# VC_Panning_Mixer_CTRL.net
KiCad netlist of a schematic drawn in EAGLE
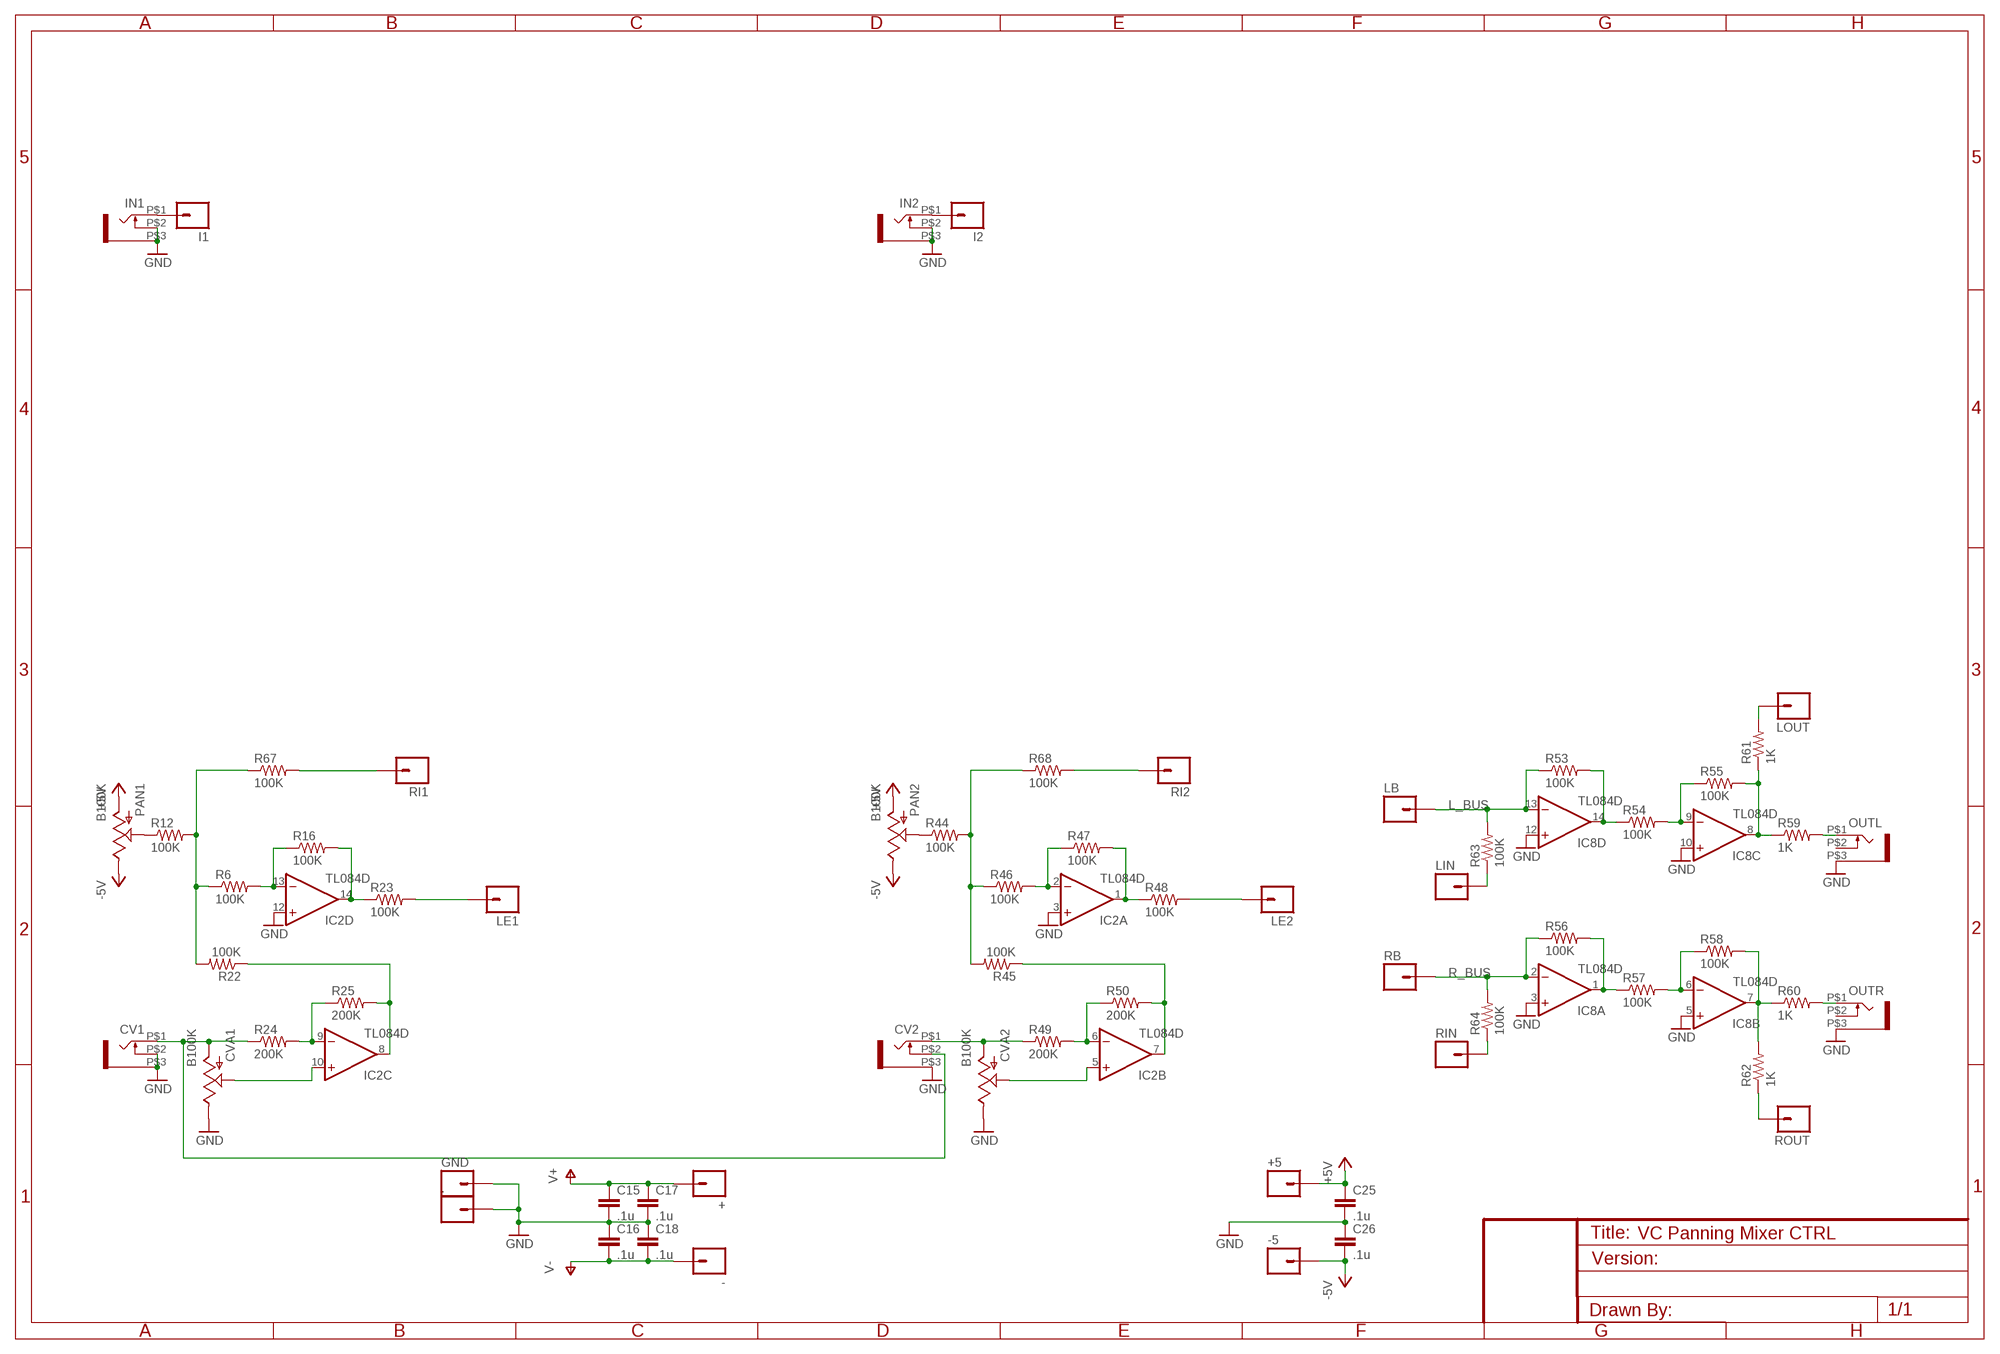
[diagram p0: schematic, sheet 1]

(export (version "E")
  (design (tool "Eeschema 10.0.6"))
  (components
    (comp (ref "+")
      (value "M01PTH")
      (footprint "eagle-import:1X01")
      (libsource (lib "eagle-import") (part "M01PTH"))
    )
    (comp (ref "+5")
      (value "M01PTH")
      (footprint "eagle-import:1X01")
      (libsource (lib "eagle-import") (part "M01PTH"))
    )
    (comp (ref "-")
      (value "M01PTH")
      (footprint "eagle-import:1X01")
      (libsource (lib "eagle-import") (part "M01PTH"))
    )
    (comp (ref "-5")
      (value "M01PTH")
      (footprint "eagle-import:1X01")
      (libsource (lib "eagle-import") (part "M01PTH"))
    )
    (comp (ref ".")
      (value "M01PTH")
      (footprint "eagle-import:1X01")
      (libsource (lib "eagle-import") (part "M01PTH"))
    )
    (comp (ref "C15")
      (value ".1u")
      (footprint "eagle-import:0805")
      (libsource (lib "eagle-import") (part "CAP0805"))
    )
    (comp (ref "C16")
      (value ".1u")
      (footprint "eagle-import:0805")
      (libsource (lib "eagle-import") (part "CAP0805"))
    )
    (comp (ref "C17")
      (value ".1u")
      (footprint "eagle-import:0805")
      (libsource (lib "eagle-import") (part "CAP0805"))
    )
    (comp (ref "C18")
      (value ".1u")
      (footprint "eagle-import:0805")
      (libsource (lib "eagle-import") (part "CAP0805"))
    )
    (comp (ref "C25")
      (value ".1u")
      (footprint "eagle-import:0805")
      (libsource (lib "eagle-import") (part "CAP0805"))
    )
    (comp (ref "C26")
      (value ".1u")
      (footprint "eagle-import:0805")
      (libsource (lib "eagle-import") (part "CAP0805"))
    )
    (comp (ref "CV1")
      (value "WQP-PJ301M-12_JACK")
      (footprint "eagle-import:WQP-PJ301M-12_JACK")
      (libsource (lib "eagle-import") (part "WQP-PJ301M-12_JACK"))
    )
    (comp (ref "CV2")
      (value "WQP-PJ301M-12_JACK")
      (footprint "eagle-import:WQP-PJ301M-12_JACK")
      (libsource (lib "eagle-import") (part "WQP-PJ301M-12_JACK"))
    )
    (comp (ref "CVA1")
      (value "B100K")
      (footprint "eagle-import:ALPS_POT")
      (libsource (lib "eagle-import") (part "POT"))
    )
    (comp (ref "CVA2")
      (value "B100K")
      (footprint "eagle-import:ALPS_POT")
      (libsource (lib "eagle-import") (part "POT"))
    )
    (comp (ref "GND")
      (value "M01PTH")
      (footprint "eagle-import:1X01")
      (libsource (lib "eagle-import") (part "M01PTH"))
    )
    (comp (ref "I1")
      (value "M01PTH")
      (footprint "eagle-import:1X01")
      (libsource (lib "eagle-import") (part "M01PTH"))
    )
    (comp (ref "I2")
      (value "M01PTH")
      (footprint "eagle-import:1X01")
      (libsource (lib "eagle-import") (part "M01PTH"))
    )
    (comp (ref "IC2")
      (value "TL084D")
      (footprint "eagle-import:SO14")
      (libsource (lib "eagle-import") (part "TL084D"))
    )
    (comp (ref "IC8")
      (value "TL084D")
      (footprint "eagle-import:SO14")
      (libsource (lib "eagle-import") (part "TL084D"))
    )
    (comp (ref "IN1")
      (value "WQP-PJ301M-12_JACK")
      (footprint "eagle-import:WQP-PJ301M-12_JACK")
      (libsource (lib "eagle-import") (part "WQP-PJ301M-12_JACK"))
    )
    (comp (ref "IN2")
      (value "WQP-PJ301M-12_JACK")
      (footprint "eagle-import:WQP-PJ301M-12_JACK")
      (libsource (lib "eagle-import") (part "WQP-PJ301M-12_JACK"))
    )
    (comp (ref "LB")
      (value "M01PTH")
      (footprint "eagle-import:1X01")
      (libsource (lib "eagle-import") (part "M01PTH"))
    )
    (comp (ref "LE1")
      (value "M01PTH")
      (footprint "eagle-import:1X01")
      (libsource (lib "eagle-import") (part "M01PTH"))
    )
    (comp (ref "LE2")
      (value "M01PTH")
      (footprint "eagle-import:1X01")
      (libsource (lib "eagle-import") (part "M01PTH"))
    )
    (comp (ref "LIN")
      (value "M01PTH")
      (footprint "eagle-import:1X01")
      (libsource (lib "eagle-import") (part "M01PTH"))
    )
    (comp (ref "LOUT")
      (value "M01PTH")
      (footprint "eagle-import:1X01")
      (libsource (lib "eagle-import") (part "M01PTH"))
    )
    (comp (ref "OUTL")
      (value "WQP-PJ301M-12_JACK")
      (footprint "eagle-import:WQP-PJ301M-12_JACK")
      (libsource (lib "eagle-import") (part "WQP-PJ301M-12_JACK"))
    )
    (comp (ref "OUTR")
      (value "WQP-PJ301M-12_JACK")
      (footprint "eagle-import:WQP-PJ301M-12_JACK")
      (libsource (lib "eagle-import") (part "WQP-PJ301M-12_JACK"))
    )
    (comp (ref "PAN1")
      (value "B100K")
      (footprint "eagle-import:ALPS_POT")
      (libsource (lib "eagle-import") (part "POT"))
    )
    (comp (ref "PAN2")
      (value "B100K")
      (footprint "eagle-import:ALPS_POT")
      (libsource (lib "eagle-import") (part "POT"))
    )
    (comp (ref "R6")
      (value "100K")
      (footprint "eagle-import:0805")
      (libsource (lib "eagle-import") (part "RESISTOR0805-RES"))
    )
    (comp (ref "R12")
      (value "100K")
      (footprint "eagle-import:0805")
      (libsource (lib "eagle-import") (part "RESISTOR0805-RES"))
    )
    (comp (ref "R16")
      (value "100K")
      (footprint "eagle-import:0805")
      (libsource (lib "eagle-import") (part "RESISTOR0805-RES"))
    )
    (comp (ref "R22")
      (value "100K")
      (footprint "eagle-import:0805")
      (libsource (lib "eagle-import") (part "RESISTOR0805-RES"))
    )
    (comp (ref "R23")
      (value "100K")
      (footprint "eagle-import:0805")
      (libsource (lib "eagle-import") (part "RESISTOR0805-RES"))
    )
    (comp (ref "R24")
      (value "200K")
      (footprint "eagle-import:0805")
      (libsource (lib "eagle-import") (part "RESISTOR0805-RES"))
    )
    (comp (ref "R25")
      (value "200K")
      (footprint "eagle-import:0805")
      (libsource (lib "eagle-import") (part "RESISTOR0805-RES"))
    )
    (comp (ref "R44")
      (value "100K")
      (footprint "eagle-import:0805")
      (libsource (lib "eagle-import") (part "RESISTOR0805-RES"))
    )
    (comp (ref "R45")
      (value "100K")
      (footprint "eagle-import:0805")
      (libsource (lib "eagle-import") (part "RESISTOR0805-RES"))
    )
    (comp (ref "R46")
      (value "100K")
      (footprint "eagle-import:0805")
      (libsource (lib "eagle-import") (part "RESISTOR0805-RES"))
    )
    (comp (ref "R47")
      (value "100K")
      (footprint "eagle-import:0805")
      (libsource (lib "eagle-import") (part "RESISTOR0805-RES"))
    )
    (comp (ref "R48")
      (value "100K")
      (footprint "eagle-import:0805")
      (libsource (lib "eagle-import") (part "RESISTOR0805-RES"))
    )
    (comp (ref "R49")
      (value "200K")
      (footprint "eagle-import:0805")
      (libsource (lib "eagle-import") (part "RESISTOR0805-RES"))
    )
    (comp (ref "R50")
      (value "200K")
      (footprint "eagle-import:0805")
      (libsource (lib "eagle-import") (part "RESISTOR0805-RES"))
    )
    (comp (ref "R53")
      (value "100K")
      (footprint "eagle-import:0805")
      (libsource (lib "eagle-import") (part "RESISTOR0805-RES"))
    )
    (comp (ref "R54")
      (value "100K")
      (footprint "eagle-import:0805")
      (libsource (lib "eagle-import") (part "RESISTOR0805-RES"))
    )
    (comp (ref "R55")
      (value "100K")
      (footprint "eagle-import:0805")
      (libsource (lib "eagle-import") (part "RESISTOR0805-RES"))
    )
    (comp (ref "R56")
      (value "100K")
      (footprint "eagle-import:0805")
      (libsource (lib "eagle-import") (part "RESISTOR0805-RES"))
    )
    (comp (ref "R57")
      (value "100K")
      (footprint "eagle-import:0805")
      (libsource (lib "eagle-import") (part "RESISTOR0805-RES"))
    )
    (comp (ref "R58")
      (value "100K")
      (footprint "eagle-import:0805")
      (libsource (lib "eagle-import") (part "RESISTOR0805-RES"))
    )
    (comp (ref "R59")
      (value "1K")
      (footprint "eagle-import:0805")
      (libsource (lib "eagle-import") (part "RESISTOR0805-RES"))
    )
    (comp (ref "R60")
      (value "1K")
      (footprint "eagle-import:0805")
      (libsource (lib "eagle-import") (part "RESISTOR0805-RES"))
    )
    (comp (ref "R61")
      (value "1K")
      (footprint "eagle-import:0805")
      (libsource (lib "eagle-import") (part "RESISTOR0805-RES"))
    )
    (comp (ref "R62")
      (value "1K")
      (footprint "eagle-import:0805")
      (libsource (lib "eagle-import") (part "RESISTOR0805-RES"))
    )
    (comp (ref "R63")
      (value "100K")
      (footprint "eagle-import:0805")
      (libsource (lib "eagle-import") (part "RESISTOR0805-RES"))
    )
    (comp (ref "R64")
      (value "100K")
      (footprint "eagle-import:0805")
      (libsource (lib "eagle-import") (part "RESISTOR0805-RES"))
    )
    (comp (ref "R67")
      (value "100K")
      (footprint "eagle-import:0805")
      (libsource (lib "eagle-import") (part "RESISTOR0805-RES"))
    )
    (comp (ref "R68")
      (value "100K")
      (footprint "eagle-import:0805")
      (libsource (lib "eagle-import") (part "RESISTOR0805-RES"))
    )
    (comp (ref "RB")
      (value "M01PTH")
      (footprint "eagle-import:1X01")
      (libsource (lib "eagle-import") (part "M01PTH"))
    )
    (comp (ref "RI1")
      (value "M01PTH")
      (footprint "eagle-import:1X01")
      (libsource (lib "eagle-import") (part "M01PTH"))
    )
    (comp (ref "RI2")
      (value "M01PTH")
      (footprint "eagle-import:1X01")
      (libsource (lib "eagle-import") (part "M01PTH"))
    )
    (comp (ref "RIN")
      (value "M01PTH")
      (footprint "eagle-import:1X01")
      (libsource (lib "eagle-import") (part "M01PTH"))
    )
    (comp (ref "ROUT")
      (value "M01PTH")
      (footprint "eagle-import:1X01")
      (libsource (lib "eagle-import") (part "M01PTH"))
    )
  )
  (nets
    (net (code "1") (name "+5V") (class "Default")
      (node (ref "+5") (pin "1") (pinfunction "1_1") (pintype "passive"))
      (node (ref "C25") (pin "1") (pinfunction "1_1") (pintype "passive"))
      (node (ref "PAN1") (pin "P$3") (pinfunction "A_P$3") (pintype "passive"))
      (node (ref "PAN2") (pin "P$3") (pinfunction "A_P$3") (pintype "passive"))
    )
    (net (code "2") (name "-5V") (class "Default")
      (node (ref "-5") (pin "1") (pinfunction "1_1") (pintype "passive"))
      (node (ref "C26") (pin "2") (pinfunction "2_2") (pintype "passive"))
      (node (ref "PAN1") (pin "P$1") (pinfunction "E_P$1") (pintype "passive"))
      (node (ref "PAN2") (pin "P$1") (pinfunction "E_P$1") (pintype "passive"))
    )
    (net (code "3") (name "/L_BUS") (class "Default")
      (node (ref "IC8") (pin "13") (pinfunction "-IN_13") (pintype "input"))
      (node (ref "LB") (pin "1") (pinfunction "1_1") (pintype "passive"))
      (node (ref "R53") (pin "1") (pinfunction "1_1") (pintype "passive"))
      (node (ref "R63") (pin "2") (pinfunction "2_2") (pintype "passive"))
    )
    (net (code "4") (name "/R_BUS") (class "Default")
      (node (ref "IC8") (pin "2") (pinfunction "-IN_2") (pintype "input"))
      (node (ref "R56") (pin "1") (pinfunction "1_1") (pintype "passive"))
      (node (ref "R64") (pin "2") (pinfunction "2_2") (pintype "passive"))
      (node (ref "RB") (pin "1") (pinfunction "1_1") (pintype "passive"))
    )
    (net (code "5") (name "GND") (class "Default")
      (node (ref ".") (pin "1") (pinfunction "1_1") (pintype "passive"))
      (node (ref "C15") (pin "2") (pinfunction "2_2") (pintype "passive"))
      (node (ref "C16") (pin "1") (pinfunction "1_1") (pintype "passive"))
      (node (ref "C17") (pin "2") (pinfunction "2_2") (pintype "passive"))
      (node (ref "C18") (pin "1") (pinfunction "1_1") (pintype "passive"))
      (node (ref "C25") (pin "2") (pinfunction "2_2") (pintype "passive"))
      (node (ref "C26") (pin "1") (pinfunction "1_1") (pintype "passive"))
      (node (ref "CV1") (pin "P$2") (pinfunction "3_P$2") (pintype "passive"))
      (node (ref "CV1") (pin "P$3") (pinfunction "1_P$3") (pintype "passive"))
      (node (ref "CV2") (pin "P$3") (pinfunction "1_P$3") (pintype "passive"))
      (node (ref "CVA1") (pin "P$1") (pinfunction "E_P$1") (pintype "passive"))
      (node (ref "CVA2") (pin "P$1") (pinfunction "E_P$1") (pintype "passive"))
      (node (ref "GND") (pin "1") (pinfunction "1_1") (pintype "passive"))
      (node (ref "IC2") (pin "12") (pinfunction "+IN_12") (pintype "input"))
      (node (ref "IC2") (pin "3") (pinfunction "+IN_3") (pintype "input"))
      (node (ref "IC8") (pin "10") (pinfunction "+IN_10") (pintype "input"))
      (node (ref "IC8") (pin "12") (pinfunction "+IN_12") (pintype "input"))
      (node (ref "IC8") (pin "3") (pinfunction "+IN_3") (pintype "input"))
      (node (ref "IC8") (pin "5") (pinfunction "+IN_5") (pintype "input"))
      (node (ref "IN1") (pin "P$2") (pinfunction "3_P$2") (pintype "passive"))
      (node (ref "IN1") (pin "P$3") (pinfunction "1_P$3") (pintype "passive"))
      (node (ref "IN2") (pin "P$2") (pinfunction "3_P$2") (pintype "passive"))
      (node (ref "IN2") (pin "P$3") (pinfunction "1_P$3") (pintype "passive"))
      (node (ref "OUTL") (pin "P$3") (pinfunction "1_P$3") (pintype "passive"))
      (node (ref "OUTR") (pin "P$3") (pinfunction "1_P$3") (pintype "passive"))
    )
    (net (code "6") (name "Net-(CV1-2)") (class "Default")
      (node (ref "CV1") (pin "P$1") (pinfunction "2_P$1") (pintype "passive"))
      (node (ref "CV2") (pin "P$2") (pinfunction "3_P$2") (pintype "passive"))
      (node (ref "CVA1") (pin "P$3") (pinfunction "A_P$3") (pintype "passive"))
      (node (ref "R24") (pin "1") (pinfunction "1_1") (pintype "passive"))
    )
    (net (code "7") (name "Net-(CV2-2)") (class "Default")
      (node (ref "CV2") (pin "P$1") (pinfunction "2_P$1") (pintype "passive"))
      (node (ref "CVA2") (pin "P$3") (pinfunction "A_P$3") (pintype "passive"))
      (node (ref "R49") (pin "1") (pinfunction "1_1") (pintype "passive"))
    )
    (net (code "8") (name "Net-(CVA1-S)") (class "Default")
      (node (ref "CVA1") (pin "P$2") (pinfunction "S_P$2") (pintype "passive"))
      (node (ref "IC2") (pin "10") (pinfunction "+IN_10") (pintype "input"))
    )
    (net (code "9") (name "Net-(CVA2-S)") (class "Default")
      (node (ref "CVA2") (pin "P$2") (pinfunction "S_P$2") (pintype "passive"))
      (node (ref "IC2") (pin "5") (pinfunction "+IN_5") (pintype "input"))
    )
    (net (code "10") (name "Net-(IC2A--IN)") (class "Default")
      (node (ref "IC2") (pin "2") (pinfunction "-IN_2") (pintype "input"))
      (node (ref "R46") (pin "2") (pinfunction "2_2") (pintype "passive"))
      (node (ref "R47") (pin "1") (pinfunction "1_1") (pintype "passive"))
    )
    (net (code "11") (name "Net-(IC2A-OUT)") (class "Default")
      (node (ref "IC2") (pin "1") (pinfunction "OUT_1") (pintype "output"))
      (node (ref "R47") (pin "2") (pinfunction "2_2") (pintype "passive"))
      (node (ref "R48") (pin "1") (pinfunction "1_1") (pintype "passive"))
    )
    (net (code "12") (name "Net-(IC2B--IN)") (class "Default")
      (node (ref "IC2") (pin "6") (pinfunction "-IN_6") (pintype "input"))
      (node (ref "R49") (pin "2") (pinfunction "2_2") (pintype "passive"))
      (node (ref "R50") (pin "1") (pinfunction "1_1") (pintype "passive"))
    )
    (net (code "13") (name "Net-(IC2B-OUT)") (class "Default")
      (node (ref "IC2") (pin "7") (pinfunction "OUT_7") (pintype "output"))
      (node (ref "R45") (pin "1") (pinfunction "1_1") (pintype "passive"))
      (node (ref "R50") (pin "2") (pinfunction "2_2") (pintype "passive"))
    )
    (net (code "14") (name "Net-(IC2C--IN)") (class "Default")
      (node (ref "IC2") (pin "9") (pinfunction "-IN_9") (pintype "input"))
      (node (ref "R24") (pin "2") (pinfunction "2_2") (pintype "passive"))
      (node (ref "R25") (pin "1") (pinfunction "1_1") (pintype "passive"))
    )
    (net (code "15") (name "Net-(IC2C-OUT)") (class "Default")
      (node (ref "IC2") (pin "8") (pinfunction "OUT_8") (pintype "output"))
      (node (ref "R22") (pin "1") (pinfunction "1_1") (pintype "passive"))
      (node (ref "R25") (pin "2") (pinfunction "2_2") (pintype "passive"))
    )
    (net (code "16") (name "Net-(IC2D--IN)") (class "Default")
      (node (ref "IC2") (pin "13") (pinfunction "-IN_13") (pintype "input"))
      (node (ref "R16") (pin "1") (pinfunction "1_1") (pintype "passive"))
      (node (ref "R6") (pin "2") (pinfunction "2_2") (pintype "passive"))
    )
    (net (code "17") (name "Net-(IC2D-OUT)") (class "Default")
      (node (ref "IC2") (pin "14") (pinfunction "OUT_14") (pintype "output"))
      (node (ref "R16") (pin "2") (pinfunction "2_2") (pintype "passive"))
      (node (ref "R23") (pin "1") (pinfunction "1_1") (pintype "passive"))
    )
    (net (code "18") (name "Net-(IC8A-OUT)") (class "Default")
      (node (ref "IC8") (pin "1") (pinfunction "OUT_1") (pintype "output"))
      (node (ref "R56") (pin "2") (pinfunction "2_2") (pintype "passive"))
      (node (ref "R57") (pin "1") (pinfunction "1_1") (pintype "passive"))
    )
    (net (code "19") (name "Net-(IC8B--IN)") (class "Default")
      (node (ref "IC8") (pin "6") (pinfunction "-IN_6") (pintype "input"))
      (node (ref "R57") (pin "2") (pinfunction "2_2") (pintype "passive"))
      (node (ref "R58") (pin "1") (pinfunction "1_1") (pintype "passive"))
    )
    (net (code "20") (name "Net-(IC8B-OUT)") (class "Default")
      (node (ref "IC8") (pin "7") (pinfunction "OUT_7") (pintype "output"))
      (node (ref "R58") (pin "2") (pinfunction "2_2") (pintype "passive"))
      (node (ref "R60") (pin "1") (pinfunction "1_1") (pintype "passive"))
      (node (ref "R62") (pin "2") (pinfunction "2_2") (pintype "passive"))
    )
    (net (code "21") (name "Net-(IC8C--IN)") (class "Default")
      (node (ref "IC8") (pin "9") (pinfunction "-IN_9") (pintype "input"))
      (node (ref "R54") (pin "2") (pinfunction "2_2") (pintype "passive"))
      (node (ref "R55") (pin "1") (pinfunction "1_1") (pintype "passive"))
    )
    (net (code "22") (name "Net-(IC8C-OUT)") (class "Default")
      (node (ref "IC8") (pin "8") (pinfunction "OUT_8") (pintype "output"))
      (node (ref "R55") (pin "2") (pinfunction "2_2") (pintype "passive"))
      (node (ref "R59") (pin "1") (pinfunction "1_1") (pintype "passive"))
      (node (ref "R61") (pin "1") (pinfunction "1_1") (pintype "passive"))
    )
    (net (code "23") (name "Net-(IC8D-OUT)") (class "Default")
      (node (ref "IC8") (pin "14") (pinfunction "OUT_14") (pintype "output"))
      (node (ref "R53") (pin "2") (pinfunction "2_2") (pintype "passive"))
      (node (ref "R54") (pin "1") (pinfunction "1_1") (pintype "passive"))
    )
    (net (code "24") (name "Net-(IN1-2)") (class "Default")
      (node (ref "I1") (pin "1") (pinfunction "1_1") (pintype "passive"))
      (node (ref "IN1") (pin "P$1") (pinfunction "2_P$1") (pintype "passive"))
    )
    (net (code "25") (name "Net-(IN2-2)") (class "Default")
      (node (ref "I2") (pin "1") (pinfunction "1_1") (pintype "passive"))
      (node (ref "IN2") (pin "P$1") (pinfunction "2_P$1") (pintype "passive"))
    )
    (net (code "26") (name "Net-(LE1-Pad1)") (class "Default")
      (node (ref "LE1") (pin "1") (pinfunction "1_1") (pintype "passive"))
      (node (ref "R23") (pin "2") (pinfunction "2_2") (pintype "passive"))
    )
    (net (code "27") (name "Net-(LE2-Pad1)") (class "Default")
      (node (ref "LE2") (pin "1") (pinfunction "1_1") (pintype "passive"))
      (node (ref "R48") (pin "2") (pinfunction "2_2") (pintype "passive"))
    )
    (net (code "28") (name "Net-(LIN-Pad1)") (class "Default")
      (node (ref "LIN") (pin "1") (pinfunction "1_1") (pintype "passive"))
      (node (ref "R63") (pin "1") (pinfunction "1_1") (pintype "passive"))
    )
    (net (code "29") (name "Net-(LOUT-Pad1)") (class "Default")
      (node (ref "LOUT") (pin "1") (pinfunction "1_1") (pintype "passive"))
      (node (ref "R61") (pin "2") (pinfunction "2_2") (pintype "passive"))
    )
    (net (code "30") (name "Net-(OUTL-2)") (class "Default")
      (node (ref "OUTL") (pin "P$1") (pinfunction "2_P$1") (pintype "passive"))
      (node (ref "R59") (pin "2") (pinfunction "2_2") (pintype "passive"))
    )
    (net (code "31") (name "Net-(OUTR-2)") (class "Default")
      (node (ref "OUTR") (pin "P$1") (pinfunction "2_P$1") (pintype "passive"))
      (node (ref "R60") (pin "2") (pinfunction "2_2") (pintype "passive"))
    )
    (net (code "32") (name "Net-(PAN1-S)") (class "Default")
      (node (ref "PAN1") (pin "P$2") (pinfunction "S_P$2") (pintype "passive"))
      (node (ref "R12") (pin "1") (pinfunction "1_1") (pintype "passive"))
    )
    (net (code "33") (name "Net-(PAN2-S)") (class "Default")
      (node (ref "PAN2") (pin "P$2") (pinfunction "S_P$2") (pintype "passive"))
      (node (ref "R44") (pin "1") (pinfunction "1_1") (pintype "passive"))
    )
    (net (code "34") (name "Net-(R12-Pad2)") (class "Default")
      (node (ref "R12") (pin "2") (pinfunction "2_2") (pintype "passive"))
      (node (ref "R22") (pin "2") (pinfunction "2_2") (pintype "passive"))
      (node (ref "R6") (pin "1") (pinfunction "1_1") (pintype "passive"))
      (node (ref "R67") (pin "1") (pinfunction "1_1") (pintype "passive"))
    )
    (net (code "35") (name "Net-(R44-Pad2)") (class "Default")
      (node (ref "R44") (pin "2") (pinfunction "2_2") (pintype "passive"))
      (node (ref "R45") (pin "2") (pinfunction "2_2") (pintype "passive"))
      (node (ref "R46") (pin "1") (pinfunction "1_1") (pintype "passive"))
      (node (ref "R68") (pin "1") (pinfunction "1_1") (pintype "passive"))
    )
    (net (code "36") (name "Net-(R62-Pad1)") (class "Default")
      (node (ref "R62") (pin "1") (pinfunction "1_1") (pintype "passive"))
      (node (ref "ROUT") (pin "1") (pinfunction "1_1") (pintype "passive"))
    )
    (net (code "37") (name "Net-(R64-Pad1)") (class "Default")
      (node (ref "R64") (pin "1") (pinfunction "1_1") (pintype "passive"))
      (node (ref "RIN") (pin "1") (pinfunction "1_1") (pintype "passive"))
    )
    (net (code "38") (name "Net-(R67-Pad2)") (class "Default")
      (node (ref "R67") (pin "2") (pinfunction "2_2") (pintype "passive"))
      (node (ref "RI1") (pin "1") (pinfunction "1_1") (pintype "passive"))
    )
    (net (code "39") (name "Net-(R68-Pad2)") (class "Default")
      (node (ref "R68") (pin "2") (pinfunction "2_2") (pintype "passive"))
      (node (ref "RI2") (pin "1") (pinfunction "1_1") (pintype "passive"))
    )
    (net (code "40") (name "V+") (class "Default")
      (node (ref "+") (pin "1") (pinfunction "1_1") (pintype "passive"))
      (node (ref "C15") (pin "1") (pinfunction "1_1") (pintype "passive"))
      (node (ref "C17") (pin "1") (pinfunction "1_1") (pintype "passive"))
    )
    (net (code "41") (name "V-") (class "Default")
      (node (ref "-") (pin "1") (pinfunction "1_1") (pintype "passive"))
      (node (ref "C16") (pin "2") (pinfunction "2_2") (pintype "passive"))
      (node (ref "C18") (pin "2") (pinfunction "2_2") (pintype "passive"))
    )
    (net (code "42") (name "unconnected-(OUTL-3-PadP$2)") (class "Default")
      (node (ref "OUTL") (pin "P$2") (pinfunction "3_P$2") (pintype "passive"))
    )
    (net (code "43") (name "unconnected-(OUTR-3-PadP$2)") (class "Default")
      (node (ref "OUTR") (pin "P$2") (pinfunction "3_P$2") (pintype "passive"))
    )
  )
)
